# Charger.net
KiCad netlist of a schematic drawn in Altium Designer
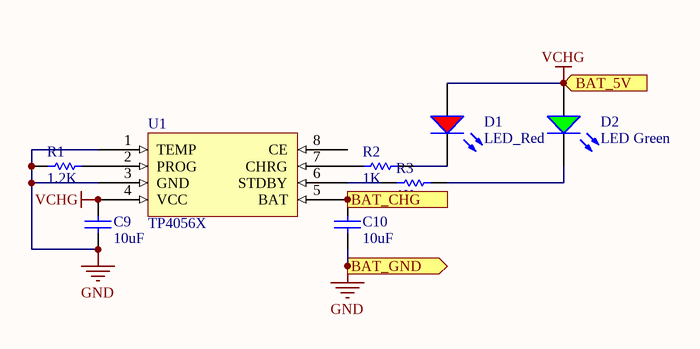
[diagram p0: Charger.SchDoc]

(export (version "E")
  (design (tool "Eeschema 10.0.6"))
  (components
    (comp (ref "C9") (value "10uF") (footprint "SMC_0805") (libsource (lib "Common") (part "Cap Ceramic")))
    (comp (ref "C10") (value "10uF") (footprint "SMC_0805") (libsource (lib "Common") (part "Cap Ceramic")))
    (comp (ref "D1") (value "LED_Red") (footprint "SMLED_0603") (libsource (lib "Common") (part "LED_Red")))
    (comp (ref "D2")
      (value "LED Green")
      (footprint "SMLED_0603")
      (libsource (lib "Common") (part "LED Green"))
    )
    (comp (ref "R1") (value "1.2K") (footprint "SMR_0402") (libsource (lib "Common") (part "Res SMT")))
    (comp (ref "R2") (value "1K") (footprint "SMR_0402") (libsource (lib "Common") (part "Res SMT")))
    (comp (ref "R3") (value "1K") (footprint "SMR_0402") (libsource (lib "Common") (part "Res SMT")))
    (comp (ref "U1")
      (value "TP4056X")
      (footprint "SOIC127P600X175_HS-9N")
      (libsource (lib "Charger") (part "TP4056X"))
    )
  )
  (nets
    (net (code "1") (name "/BAT_CHG") (class "Default")
      (node (ref "C10") (pin "2") (pinfunction "2_2") (pintype "passive"))
      (node (ref "U1") (pin "5") (pinfunction "BAT_5") (pintype "input"))
    )
    (net (code "2") (name "GND") (class "Default")
      (node (ref "C10") (pin "1") (pinfunction "1_1") (pintype "passive"))
      (node (ref "C9") (pin "1") (pinfunction "1_1") (pintype "passive"))
      (node (ref "R1") (pin "1") (pinfunction "1_1") (pintype "passive"))
      (node (ref "U1") (pin "1") (pinfunction "TEMP_1") (pintype "input"))
      (node (ref "U1") (pin "3") (pinfunction "GND_3") (pintype "input"))
    )
    (net (code "3") (name "Net-(D1-PadK)") (class "Default")
      (node (ref "D1") (pin "K") (pinfunction "K_K") (pintype "passive"))
      (node (ref "R2") (pin "2") (pinfunction "2_2") (pintype "passive"))
    )
    (net (code "4") (name "Net-(D2-PadK)") (class "Default")
      (node (ref "D2") (pin "K") (pinfunction "K_K") (pintype "passive"))
      (node (ref "R3") (pin "2") (pinfunction "2_2") (pintype "passive"))
    )
    (net (code "5") (name "Net-(U1-CHRG)") (class "Default")
      (node (ref "R2") (pin "1") (pinfunction "1_1") (pintype "passive"))
      (node (ref "U1") (pin "7") (pinfunction "CHRG_7") (pintype "input"))
    )
    (net (code "6") (name "Net-(U1-PROG)") (class "Default")
      (node (ref "R1") (pin "2") (pinfunction "2_2") (pintype "passive"))
      (node (ref "U1") (pin "2") (pinfunction "PROG_2") (pintype "input"))
    )
    (net (code "7") (name "Net-(U1-STDBY)") (class "Default")
      (node (ref "R3") (pin "1") (pinfunction "1_1") (pintype "passive"))
      (node (ref "U1") (pin "6") (pinfunction "STDBY_6") (pintype "input"))
    )
    (net (code "8") (name "VCHG") (class "Default")
      (node (ref "C9") (pin "2") (pinfunction "2_2") (pintype "passive"))
      (node (ref "D1") (pin "A") (pinfunction "A_A") (pintype "passive"))
      (node (ref "D2") (pin "A") (pinfunction "A_A") (pintype "passive"))
      (node (ref "U1") (pin "4") (pinfunction "VCC_4") (pintype "input"))
    )
    (net (code "9") (name "unconnected-(U1-CE-Pad8)") (class "Default")
      (node (ref "U1") (pin "8") (pinfunction "CE_8") (pintype "input"))
    )
  )
)
